# Thermometers.net
KiCad netlist of a schematic drawn in Altium Designer
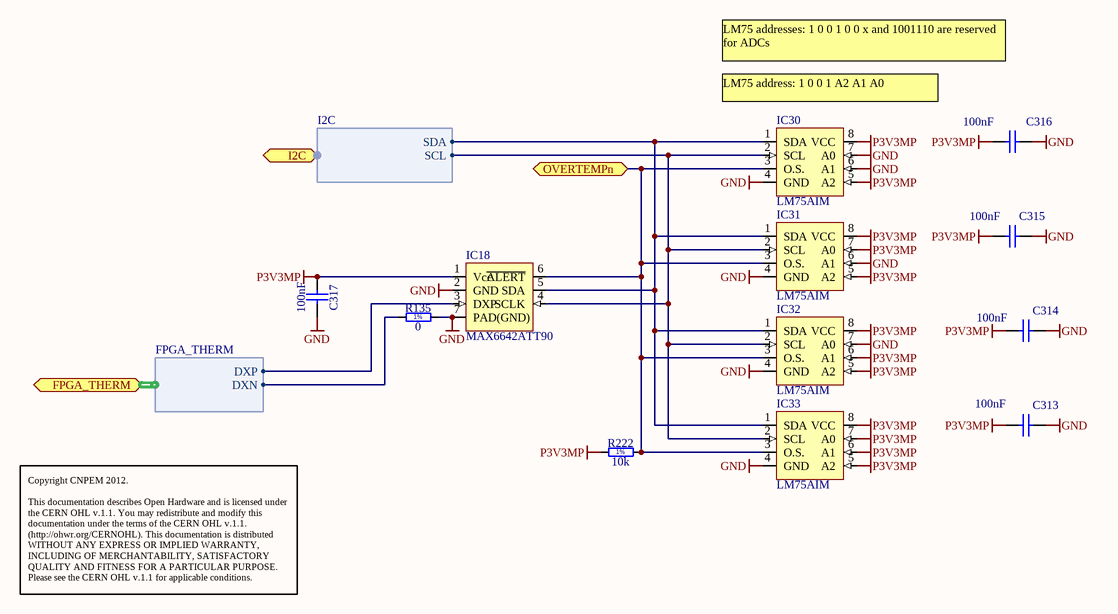
[diagram p0: Thermometers.SchDoc]

(export (version "E")
  (design (tool "Eeschema 10.0.6"))
  (components
    (comp (ref "C313")
      (value "100nF")
      (footprint "CAPC0603X33N")
      (description "Non-polarised capacitor")
      (fields
        (field (name "PART NUMBER") "CC0201_100NF_6.3V_10%_X5R")
        (field (name "VOLTAGE") "6.3V")
        (field (name "AUTHOR") "CERN DEM JLC")
      )
      (libsource (lib "Capacitors") (part "Capacitor - non polarized"))
    )
    (comp (ref "C314")
      (value "100nF")
      (footprint "CAPC0603X33N")
      (description "Non-polarised capacitor")
      (fields
        (field (name "PART NUMBER") "CC0201_100NF_6.3V_10%_X5R")
        (field (name "VOLTAGE") "6.3V")
        (field (name "AUTHOR") "CERN DEM JLC")
      )
      (libsource (lib "Capacitors") (part "Capacitor - non polarized"))
    )
    (comp (ref "C315")
      (value "100nF")
      (footprint "CAPC0603X33N")
      (description "Non-polarised capacitor")
      (fields
        (field (name "PART NUMBER") "CC0201_100NF_6.3V_10%_X5R")
        (field (name "VOLTAGE") "6.3V")
        (field (name "AUTHOR") "CERN DEM JLC")
      )
      (libsource (lib "Capacitors") (part "Capacitor - non polarized"))
    )
    (comp (ref "C316")
      (value "100nF")
      (footprint "CAPC0603X33N")
      (description "Non-polarised capacitor")
      (fields
        (field (name "PART NUMBER") "CC0201_100NF_6.3V_10%_X5R")
        (field (name "VOLTAGE") "6.3V")
        (field (name "AUTHOR") "CERN DEM JLC")
      )
      (libsource (lib "Capacitors") (part "Capacitor - non polarized"))
    )
    (comp (ref "C317")
      (value "100nF")
      (footprint "CAPC0603X33N")
      (description "Non-polarised capacitor")
      (fields
        (field (name "PART NUMBER") "CC0201_100NF_6.3V_10%_X5R")
        (field (name "VOLTAGE") "6.3V")
        (field (name "AUTHOR") "CERN DEM JLC")
      )
      (libsource (lib "Capacitors") (part "Capacitor - non polarized"))
    )
    (comp (ref "IC18")
      (value "MAX6642ATT90")
      (footprint "TFDN6")
      (description "±1°C, SMBus- Remote/Local Temperature Sensor with Overtemperature Alarm")
      (libsource (lib "LIBRARY_SCH") (part "SENS_MAX6642"))
    )
    (comp (ref "IC30")
      (value "LM75AIM")
      (footprint "SOIC127P600X175-8N")
      (description "I2C temperature sensor")
      (libsource (lib "LIBRARY_SCH") (part "SENS_LM75"))
    )
    (comp (ref "IC31")
      (value "LM75AIM")
      (footprint "SOIC127P600X175-8N")
      (description "I2C temperature sensor")
      (libsource (lib "LIBRARY_SCH") (part "SENS_LM75"))
    )
    (comp (ref "IC32")
      (value "LM75AIM")
      (footprint "SOIC127P600X175-8N")
      (description "I2C temperature sensor")
      (libsource (lib "LIBRARY_SCH") (part "SENS_LM75"))
    )
    (comp (ref "IC33")
      (value "LM75AIM")
      (footprint "SOIC127P600X175-8N")
      (description "I2C temperature sensor")
      (libsource (lib "LIBRARY_SCH") (part "SENS_LM75"))
    )
    (comp (ref "R135")
      (value "0")
      (footprint "RESC1005X40N")
      (description "Resistor - 1%")
      (fields
        (field (name "PART NUMBER") "R0402_0R_JUMPER")
        (field (name "MANUFACTURER") "GENERIC")
        (field (name "AUTHOR") "CERN DEM JLC")
      )
      (libsource (lib "Resistors") (part "Resistor - 1%"))
    )
    (comp (ref "R222")
      (value "10k")
      (footprint "RESC1005X40N")
      (description "Resistor - 1%")
      (fields
        (field (name "PART NUMBER") "R0402_10K_1%_0.0625W_100PPM")
        (field (name "POWER") "0.0625W")
        (field (name "AUTHOR") "CERN DEM JLC")
      )
      (libsource (lib "Resistors") (part "Resistor - 1%"))
    )
  )
  (nets
    (net (code "3") (name "/DXN") (class "Default")
      (node (ref "R135") (pin "1") (pinfunction "1_1") (pintype "passive"))
    )
    (net (code "4") (name "/DXP") (class "Default")
      (node (ref "IC18") (pin "3") (pinfunction "DXP_3") (pintype "input"))
    )
    (net (code "5") (name "/OVERTEMPn") (class "Default")
      (node (ref "IC18") (pin "6") (pinfunction "~{ALERT}_6") (pintype "open_collector"))
      (node (ref "IC30") (pin "3") (pinfunction "O.S._3") (pintype "open_collector"))
      (node (ref "IC31") (pin "3") (pinfunction "O.S._3") (pintype "open_collector"))
      (node (ref "IC32") (pin "3") (pinfunction "O.S._3") (pintype "open_collector"))
      (node (ref "IC33") (pin "3") (pinfunction "O.S._3") (pintype "open_collector"))
      (node (ref "R222") (pin "2") (pinfunction "2_2") (pintype "passive"))
    )
    (net (code "6") (name "/SCL") (class "Default")
      (node (ref "IC18") (pin "4") (pinfunction "SCLK_4") (pintype "input"))
      (node (ref "IC30") (pin "2") (pinfunction "SCL_2") (pintype "input"))
      (node (ref "IC31") (pin "2") (pinfunction "SCL_2") (pintype "input"))
      (node (ref "IC32") (pin "2") (pinfunction "SCL_2") (pintype "input"))
      (node (ref "IC33") (pin "2") (pinfunction "SCL_2") (pintype "input"))
    )
    (net (code "7") (name "/SDA") (class "Default")
      (node (ref "IC18") (pin "5") (pinfunction "SDA_5") (pintype "bidirectional"))
      (node (ref "IC30") (pin "1") (pinfunction "SDA_1") (pintype "bidirectional"))
      (node (ref "IC31") (pin "1") (pinfunction "SDA_1") (pintype "bidirectional"))
      (node (ref "IC32") (pin "1") (pinfunction "SDA_1") (pintype "bidirectional"))
      (node (ref "IC33") (pin "1") (pinfunction "SDA_1") (pintype "bidirectional"))
    )
    (net (code "10") (name "GND") (class "Default")
      (node (ref "C313") (pin "2") (pinfunction "2_2") (pintype "passive"))
      (node (ref "C314") (pin "2") (pinfunction "2_2") (pintype "passive"))
      (node (ref "C315") (pin "2") (pinfunction "2_2") (pintype "passive"))
      (node (ref "C316") (pin "2") (pinfunction "2_2") (pintype "passive"))
      (node (ref "C317") (pin "2") (pinfunction "2_2") (pintype "passive"))
      (node (ref "IC18") (pin "2") (pinfunction "GND_2") (pintype "power_in"))
      (node (ref "IC18") (pin "7") (pinfunction "PAD(GND)_7") (pintype "power_in"))
      (node (ref "IC30") (pin "4") (pinfunction "GND_4") (pintype "power_in"))
      (node (ref "IC30") (pin "6") (pinfunction "A1_6") (pintype "input"))
      (node (ref "IC30") (pin "7") (pinfunction "A0_7") (pintype "input"))
      (node (ref "IC31") (pin "4") (pinfunction "GND_4") (pintype "power_in"))
      (node (ref "IC31") (pin "6") (pinfunction "A1_6") (pintype "input"))
      (node (ref "IC32") (pin "4") (pinfunction "GND_4") (pintype "power_in"))
      (node (ref "IC32") (pin "7") (pinfunction "A0_7") (pintype "input"))
      (node (ref "IC33") (pin "4") (pinfunction "GND_4") (pintype "power_in"))
      (node (ref "R135") (pin "2") (pinfunction "2_2") (pintype "passive"))
    )
    (net (code "11") (name "P3V3MP") (class "Default")
      (node (ref "C313") (pin "1") (pinfunction "1_1") (pintype "passive"))
      (node (ref "C314") (pin "1") (pinfunction "1_1") (pintype "passive"))
      (node (ref "C315") (pin "1") (pinfunction "1_1") (pintype "passive"))
      (node (ref "C316") (pin "1") (pinfunction "1_1") (pintype "passive"))
      (node (ref "C317") (pin "1") (pinfunction "1_1") (pintype "passive"))
      (node (ref "IC18") (pin "1") (pinfunction "Vcc_1") (pintype "power_in"))
      (node (ref "IC30") (pin "5") (pinfunction "A2_5") (pintype "input"))
      (node (ref "IC30") (pin "8") (pinfunction "VCC_8") (pintype "power_in"))
      (node (ref "IC31") (pin "5") (pinfunction "A2_5") (pintype "input"))
      (node (ref "IC31") (pin "7") (pinfunction "A0_7") (pintype "input"))
      (node (ref "IC31") (pin "8") (pinfunction "VCC_8") (pintype "power_in"))
      (node (ref "IC32") (pin "5") (pinfunction "A2_5") (pintype "input"))
      (node (ref "IC32") (pin "6") (pinfunction "A1_6") (pintype "input"))
      (node (ref "IC32") (pin "8") (pinfunction "VCC_8") (pintype "power_in"))
      (node (ref "IC33") (pin "5") (pinfunction "A2_5") (pintype "input"))
      (node (ref "IC33") (pin "6") (pinfunction "A1_6") (pintype "input"))
      (node (ref "IC33") (pin "7") (pinfunction "A0_7") (pintype "input"))
      (node (ref "IC33") (pin "8") (pinfunction "VCC_8") (pintype "power_in"))
      (node (ref "R222") (pin "1") (pinfunction "1_1") (pintype "passive"))
    )
  )
)
